# esp8255-full-breakout.net
KiCad netlist of a schematic drawn in EAGLE
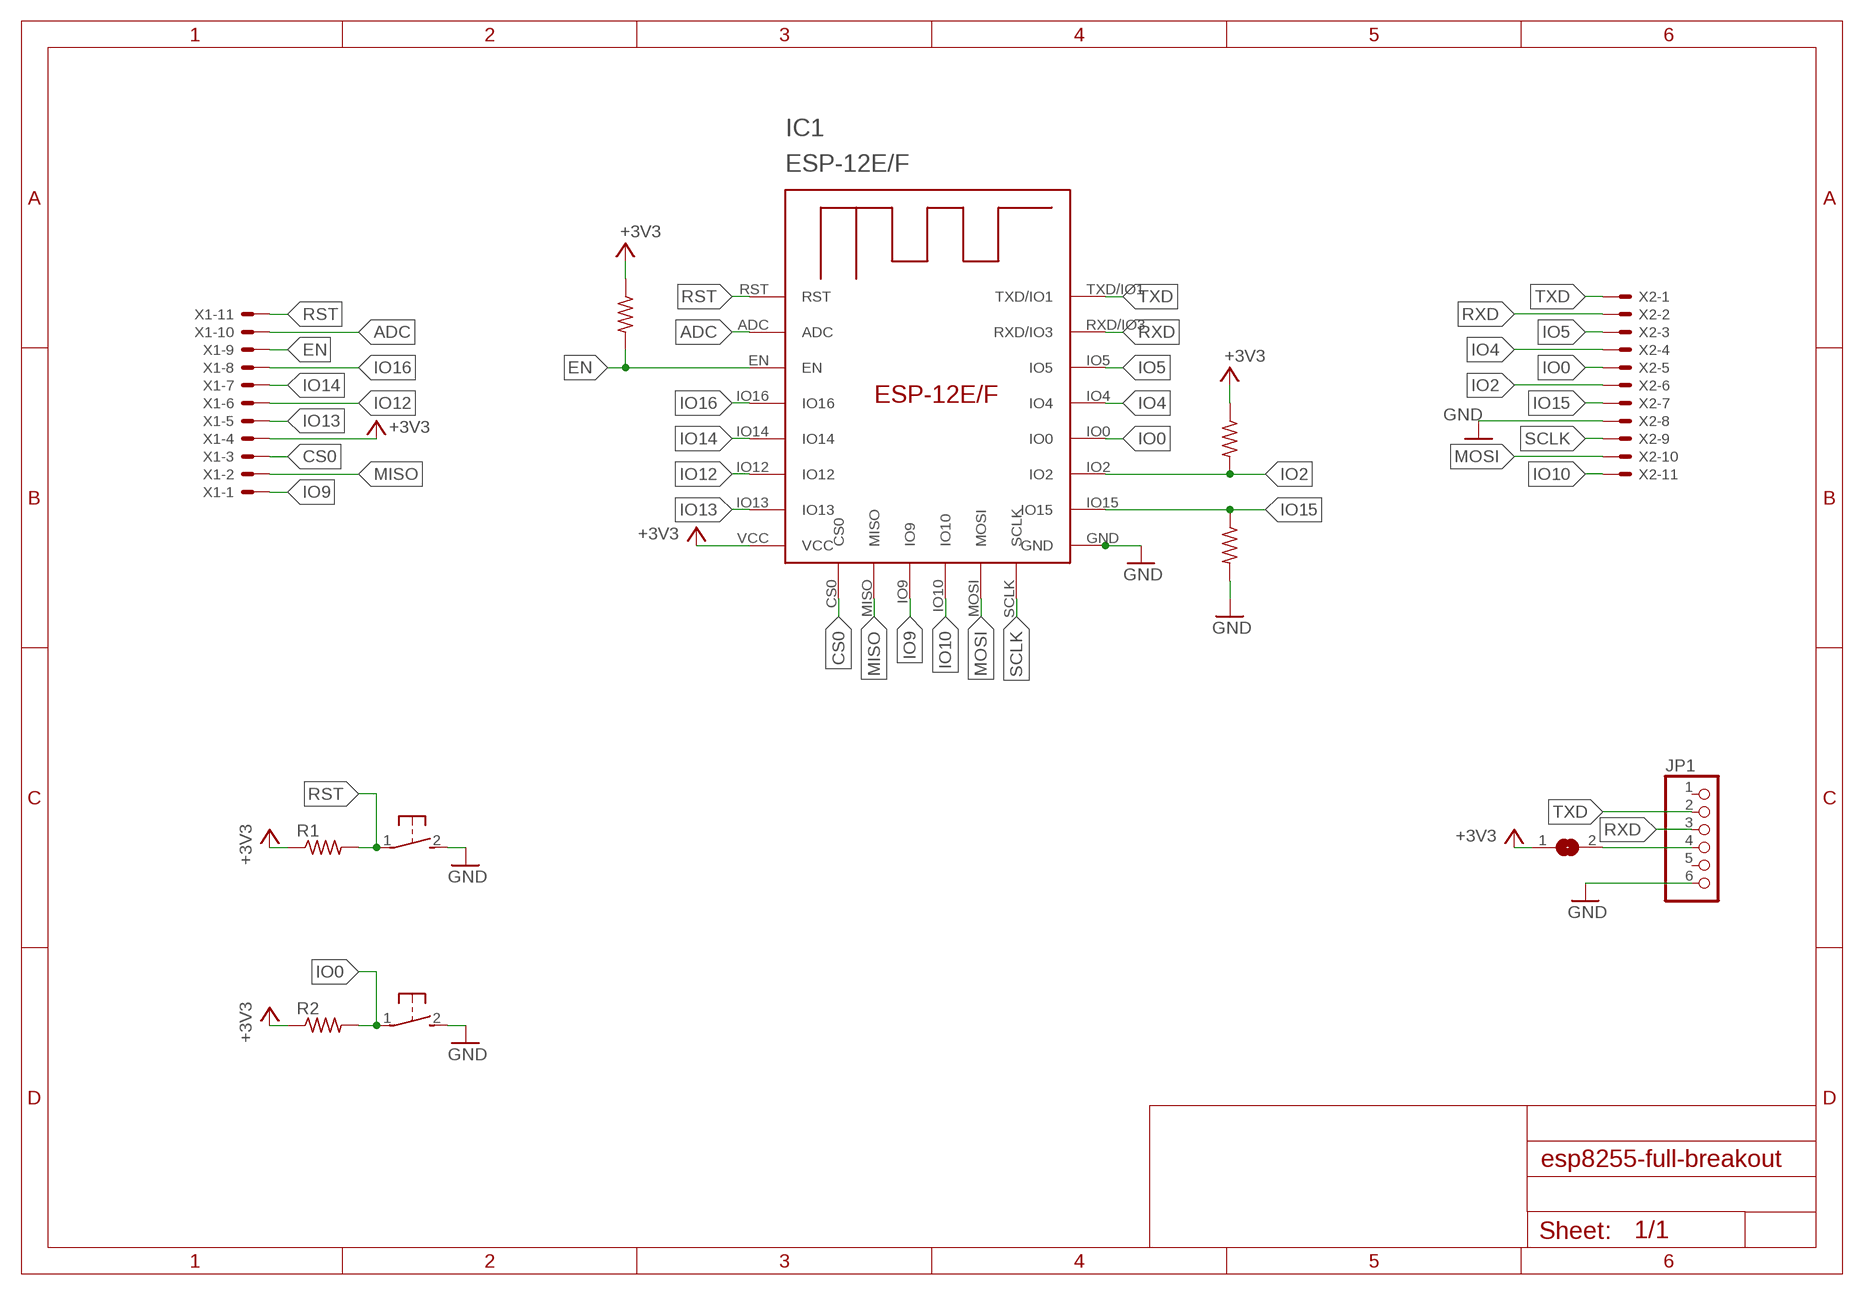
[diagram p0: schematic, sheet 1]

(export (version "E")
  (design (tool "Eeschema 10.0.6"))
  (components
    (comp (ref "IC1")
      (value "ESP-12E/F")
      (footprint "eagle-import:ESP-12E")
      (libsource (lib "eagle-import") (part "ESP-12E/F"))
    )
    (comp (ref "JP1")
      (value "PINHD-1X6B")
      (footprint "eagle-import:1X06-BIG")
      (libsource (lib "eagle-import") (part "PINHD-1X6B"))
    )
    (comp (ref "R1")
      (value "R-US_R1206")
      (footprint "eagle-import:R1206")
      (libsource (lib "eagle-import") (part "R-US_R1206"))
    )
    (comp (ref "R2")
      (value "R-US_R1206")
      (footprint "eagle-import:R1206")
      (libsource (lib "eagle-import") (part "R-US_R1206"))
    )
    (comp (ref "R3")
      (value "R-US_R1206")
      (footprint "eagle-import:R1206")
      (libsource (lib "eagle-import") (part "R-US_R1206"))
    )
    (comp (ref "R4")
      (value "R-US_R1206")
      (footprint "eagle-import:R1206")
      (libsource (lib "eagle-import") (part "R-US_R1206"))
    )
    (comp (ref "R5")
      (value "R-US_R1206")
      (footprint "eagle-import:R1206")
      (libsource (lib "eagle-import") (part "R-US_R1206"))
    )
    (comp (ref "S1")
      (value "DTSM-3")
      (footprint "eagle-import:DTSM-3")
      (libsource (lib "eagle-import") (part "DTSM-3"))
    )
    (comp (ref "S2")
      (value "DTSM-3")
      (footprint "eagle-import:DTSM-3")
      (libsource (lib "eagle-import") (part "DTSM-3"))
    )
    (comp (ref "SJ1") (value "SJ") (footprint "eagle-import:SJ") (libsource (lib "eagle-import") (part "SJ")))
    (comp (ref "X1")
      (value "JST-XH-11-PIN-ROUND-PAD")
      (footprint "eagle-import:JST-XH-11-PACKAGE-ROUND-PAD")
      (libsource (lib "eagle-import") (part "JST-XH-11-PIN-ROUND-PAD"))
    )
    (comp (ref "X2")
      (value "JST-XH-11-PIN-ROUND-PAD")
      (footprint "eagle-import:JST-XH-11-PACKAGE-ROUND-PAD")
      (libsource (lib "eagle-import") (part "JST-XH-11-PIN-ROUND-PAD"))
    )
  )
  (nets
    (net (code "1") (name "+3V3") (class "Default")
      (node (ref "IC1") (pin "VCC") (pinfunction "VCC_VCC") (pintype "power_in"))
      (node (ref "R1") (pin "1") (pinfunction "1_1") (pintype "passive"))
      (node (ref "R2") (pin "1") (pinfunction "1_1") (pintype "passive"))
      (node (ref "R4") (pin "1") (pinfunction "1_1") (pintype "passive"))
      (node (ref "R5") (pin "1") (pinfunction "1_1") (pintype "passive"))
      (node (ref "SJ1") (pin "1") (pinfunction "1_1") (pintype "passive"))
      (node (ref "X1") (pin "4") (pinfunction "S_4") (pintype "passive"))
    )
    (net (code "2") (name "ADC") (class "Default")
      (node (ref "IC1") (pin "ADC") (pinfunction "ADC_ADC") (pintype "bidirectional"))
      (node (ref "X1") (pin "10") (pinfunction "S_10") (pintype "passive"))
    )
    (net (code "3") (name "CS0") (class "Default")
      (node (ref "IC1") (pin "CS0") (pinfunction "CS0_CS0") (pintype "bidirectional"))
      (node (ref "X1") (pin "3") (pinfunction "S_3") (pintype "passive"))
    )
    (net (code "4") (name "EN") (class "Default")
      (node (ref "IC1") (pin "EN") (pinfunction "EN_EN") (pintype "bidirectional"))
      (node (ref "R5") (pin "2") (pinfunction "2_2") (pintype "passive"))
      (node (ref "X1") (pin "9") (pinfunction "S_9") (pintype "passive"))
    )
    (net (code "5") (name "GND") (class "Default")
      (node (ref "IC1") (pin "GND") (pinfunction "GND_GND") (pintype "power_in"))
      (node (ref "JP1") (pin "6") (pinfunction "6_6") (pintype "passive"))
      (node (ref "R3") (pin "2") (pinfunction "2_2") (pintype "passive"))
      (node (ref "S1") (pin "2") (pinfunction "2_2") (pintype "passive"))
      (node (ref "S2") (pin "2") (pinfunction "2_2") (pintype "passive"))
      (node (ref "X2") (pin "8") (pinfunction "S_8") (pintype "passive"))
    )
    (net (code "6") (name "IO0") (class "Default")
      (node (ref "IC1") (pin "IO0") (pinfunction "IO0_IO0") (pintype "bidirectional"))
      (node (ref "R2") (pin "2") (pinfunction "2_2") (pintype "passive"))
      (node (ref "S2") (pin "1") (pinfunction "1_1") (pintype "passive"))
      (node (ref "X2") (pin "5") (pinfunction "S_5") (pintype "passive"))
    )
    (net (code "7") (name "IO2") (class "Default")
      (node (ref "IC1") (pin "IO2") (pinfunction "IO2_IO2") (pintype "bidirectional"))
      (node (ref "R4") (pin "2") (pinfunction "2_2") (pintype "passive"))
      (node (ref "X2") (pin "6") (pinfunction "S_6") (pintype "passive"))
    )
    (net (code "8") (name "IO4") (class "Default")
      (node (ref "IC1") (pin "IO4") (pinfunction "IO4_IO4") (pintype "bidirectional"))
      (node (ref "X2") (pin "4") (pinfunction "S_4") (pintype "passive"))
    )
    (net (code "9") (name "IO5") (class "Default")
      (node (ref "IC1") (pin "IO5") (pinfunction "IO5_IO5") (pintype "bidirectional"))
      (node (ref "X2") (pin "3") (pinfunction "S_3") (pintype "passive"))
    )
    (net (code "10") (name "IO9") (class "Default")
      (node (ref "IC1") (pin "IO9") (pinfunction "IO9_IO9") (pintype "bidirectional"))
      (node (ref "X1") (pin "1") (pinfunction "S_1") (pintype "passive"))
    )
    (net (code "11") (name "IO10") (class "Default")
      (node (ref "IC1") (pin "IO10") (pinfunction "IO10_IO10") (pintype "bidirectional"))
      (node (ref "X2") (pin "11") (pinfunction "S_11") (pintype "passive"))
    )
    (net (code "12") (name "IO12") (class "Default")
      (node (ref "IC1") (pin "IO12") (pinfunction "IO12_IO12") (pintype "bidirectional"))
      (node (ref "X1") (pin "6") (pinfunction "S_6") (pintype "passive"))
    )
    (net (code "13") (name "IO13") (class "Default")
      (node (ref "IC1") (pin "IO13") (pinfunction "IO13_IO13") (pintype "bidirectional"))
      (node (ref "X1") (pin "5") (pinfunction "S_5") (pintype "passive"))
    )
    (net (code "14") (name "IO14") (class "Default")
      (node (ref "IC1") (pin "IO14") (pinfunction "IO14_IO14") (pintype "bidirectional"))
      (node (ref "X1") (pin "7") (pinfunction "S_7") (pintype "passive"))
    )
    (net (code "15") (name "IO15") (class "Default")
      (node (ref "IC1") (pin "IO15") (pinfunction "IO15_IO15") (pintype "bidirectional"))
      (node (ref "R3") (pin "1") (pinfunction "1_1") (pintype "passive"))
      (node (ref "X2") (pin "7") (pinfunction "S_7") (pintype "passive"))
    )
    (net (code "16") (name "IO16") (class "Default")
      (node (ref "IC1") (pin "IO16") (pinfunction "IO16_IO16") (pintype "bidirectional"))
      (node (ref "X1") (pin "8") (pinfunction "S_8") (pintype "passive"))
    )
    (net (code "17") (name "MISO") (class "Default")
      (node (ref "IC1") (pin "MISO") (pinfunction "MISO_MISO") (pintype "bidirectional"))
      (node (ref "X1") (pin "2") (pinfunction "S_2") (pintype "passive"))
    )
    (net (code "18") (name "MOSI") (class "Default")
      (node (ref "IC1") (pin "MOSI") (pinfunction "MOSI_MOSI") (pintype "bidirectional"))
      (node (ref "X2") (pin "10") (pinfunction "S_10") (pintype "passive"))
    )
    (net (code "19") (name "Net-(JP1-Pad4)") (class "Default")
      (node (ref "JP1") (pin "4") (pinfunction "4_4") (pintype "passive"))
      (node (ref "SJ1") (pin "2") (pinfunction "2_2") (pintype "passive"))
    )
    (net (code "20") (name "RST") (class "Default")
      (node (ref "IC1") (pin "RST") (pinfunction "RST_RST") (pintype "input"))
      (node (ref "R1") (pin "2") (pinfunction "2_2") (pintype "passive"))
      (node (ref "S1") (pin "1") (pinfunction "1_1") (pintype "passive"))
      (node (ref "X1") (pin "11") (pinfunction "S_11") (pintype "passive"))
    )
    (net (code "21") (name "RXD") (class "Default")
      (node (ref "IC1") (pin "RXD/IO3") (pinfunction "RXD/IO3_RXD/IO3") (pintype "bidirectional"))
      (node (ref "JP1") (pin "3") (pinfunction "3_3") (pintype "passive"))
      (node (ref "X2") (pin "2") (pinfunction "S_2") (pintype "passive"))
    )
    (net (code "22") (name "SCLK") (class "Default")
      (node (ref "IC1") (pin "SCLK") (pinfunction "SCLK_SCLK") (pintype "bidirectional"))
      (node (ref "X2") (pin "9") (pinfunction "S_9") (pintype "passive"))
    )
    (net (code "23") (name "TXD") (class "Default")
      (node (ref "IC1") (pin "TXD/IO1") (pinfunction "TXD/IO1_TXD/IO1") (pintype "bidirectional"))
      (node (ref "JP1") (pin "2") (pinfunction "2_2") (pintype "passive"))
      (node (ref "X2") (pin "1") (pinfunction "S_1") (pintype "passive"))
    )
    (net (code "24") (name "unconnected-(JP1-Pad1)") (class "Default")
      (node (ref "JP1") (pin "1") (pinfunction "1_1") (pintype "passive"))
    )
    (net (code "25") (name "unconnected-(JP1-Pad5)") (class "Default")
      (node (ref "JP1") (pin "5") (pinfunction "5_5") (pintype "passive"))
    )
  )
)
